# 0_2-3_3VR.net
KiCad netlist of a schematic drawn in Altium Designer
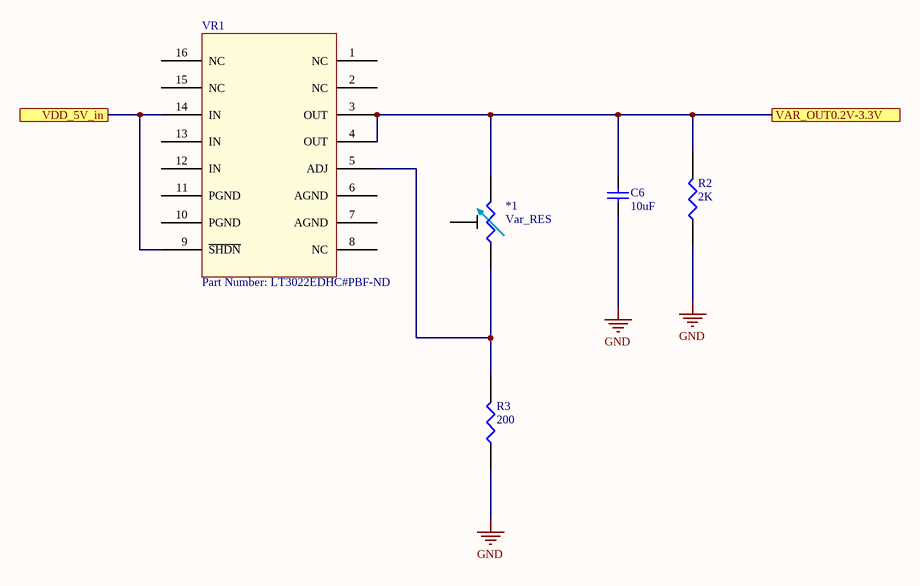
[diagram p0: 0.2-3.3VR.SchDoc]

(export (version "E")
  (design (tool "Eeschema 10.0.6"))
  (components
    (comp (ref "*1")
      (value "Var_RES")
      (footprint "res_var_5turn")
      (libsource (lib "CLS_Library") (part "Var_RES"))
    )
    (comp (ref "C6")
      (value "10uF")
      (footprint "CLS_Library:C0805")
      (description "Cap 10uF")
      (fields
        (field (name "MANUFACTURER") "Taiyo Yuden")
        (field (name "MANUFACTURER PART NUMBER") "UMK212SD103KD-T")
      )
      (libsource (lib "Chip1_TestBoard") (part "Cap 10uF"))
    )
    (comp (ref "R2")
      (value "2K")
      (description "RES SMD 2K OHM 5% 1/4W 0805")
      (fields
        (field (name "MANUFACTURER") "Stackpole Electronics")
        (field (name "MANUFACTURER PART NUMBER") "RPC0805JT2K00")
      )
      (libsource (lib "Chip1_TestBoard") (part "Res 2k"))
    )
    (comp (ref "R3")
      (value "200")
      (description "Res Thick Film 0805 200 Ohm 1% 1/8W 100ppm/C Molded SMD SMD Paper Tape on Plastic Reel")
      (fields
        (field (name "MANUFACTURER") "Bourns")
        (field (name "MANUFACTURER PART NUMBER") "CR0805-FX-2000ELF")
      )
      (libsource (lib "Chip1_TestBoard") (part "Res 200"))
    )
    (comp (ref "VR1")
      (value "Part Number: LT3022EDHC#PBF-ND")
      (footprint "LT3022")
      (description "Linear Voltage Regulator IC Positive Adjustable 1 Output 1A 16-DFN (5x3)")
      (libsource (lib "CLS_Library") (part "LT3022"))
    )
  )
  (nets
    (net (code "1") (name "/VAR_OUT0.2V-3.3V") (class "Default")
      (node (ref "*1") (pin "3") (pinfunction "3_3") (pintype "passive"))
      (node (ref "C6") (pin "2") (pinfunction "2_2") (pintype "passive"))
      (node (ref "R2") (pin "2") (pinfunction "2_2") (pintype "passive"))
      (node (ref "VR1") (pin "3") (pinfunction "OUT_3") (pintype "passive"))
      (node (ref "VR1") (pin "4") (pinfunction "OUT_4") (pintype "passive"))
    )
    (net (code "2") (name "/VDD_5V_in") (class "Default")
      (node (ref "VR1") (pin "14") (pinfunction "IN_14") (pintype "passive"))
      (node (ref "VR1") (pin "9") (pinfunction "~{SHDN}_9") (pintype "passive"))
    )
    (net (code "3") (name "GND") (class "Default")
      (node (ref "C6") (pin "1") (pinfunction "1_1") (pintype "passive"))
      (node (ref "R2") (pin "1") (pinfunction "1_1") (pintype "passive"))
      (node (ref "R3") (pin "1") (pinfunction "1_1") (pintype "passive"))
    )
    (net (code "4") (name "Net-(VR1-ADJ)") (class "Default")
      (node (ref "*1") (pin "1") (pinfunction "1_1") (pintype "passive"))
      (node (ref "R3") (pin "2") (pinfunction "2_2") (pintype "passive"))
      (node (ref "VR1") (pin "5") (pinfunction "ADJ_5") (pintype "passive"))
    )
    (net (code "5") (name "unconnected-(*1-Pad2)") (class "Default")
      (node (ref "*1") (pin "2") (pinfunction "2_2") (pintype "passive"))
    )
    (net (code "6") (name "unconnected-(VR1-AGND-Pad6)") (class "Default")
      (node (ref "VR1") (pin "6") (pinfunction "AGND_6") (pintype "passive"))
    )
    (net (code "7") (name "unconnected-(VR1-AGND-Pad7)") (class "Default")
      (node (ref "VR1") (pin "7") (pinfunction "AGND_7") (pintype "passive"))
    )
    (net (code "8") (name "unconnected-(VR1-IN-Pad12)") (class "Default")
      (node (ref "VR1") (pin "12") (pinfunction "IN_12") (pintype "passive"))
    )
    (net (code "9") (name "unconnected-(VR1-IN-Pad13)") (class "Default")
      (node (ref "VR1") (pin "13") (pinfunction "IN_13") (pintype "passive"))
    )
    (net (code "10") (name "unconnected-(VR1-NC-Pad1)") (class "Default")
      (node (ref "VR1") (pin "1") (pinfunction "NC_1") (pintype "passive"))
    )
    (net (code "11") (name "unconnected-(VR1-NC-Pad2)") (class "Default")
      (node (ref "VR1") (pin "2") (pinfunction "NC_2") (pintype "passive"))
    )
    (net (code "12") (name "unconnected-(VR1-NC-Pad8)") (class "Default")
      (node (ref "VR1") (pin "8") (pinfunction "NC_8") (pintype "passive"))
    )
    (net (code "13") (name "unconnected-(VR1-NC-Pad15)") (class "Default")
      (node (ref "VR1") (pin "15") (pinfunction "NC_15") (pintype "passive"))
    )
    (net (code "14") (name "unconnected-(VR1-NC-Pad16)") (class "Default")
      (node (ref "VR1") (pin "16") (pinfunction "NC_16") (pintype "passive"))
    )
    (net (code "15") (name "unconnected-(VR1-PGND-Pad10)") (class "Default")
      (node (ref "VR1") (pin "10") (pinfunction "PGND_10") (pintype "passive"))
    )
    (net (code "16") (name "unconnected-(VR1-PGND-Pad11)") (class "Default")
      (node (ref "VR1") (pin "11") (pinfunction "PGND_11") (pintype "passive"))
    )
  )
)
